# dw-probe-v1_0.net
KiCad netlist of a schematic drawn in EAGLE
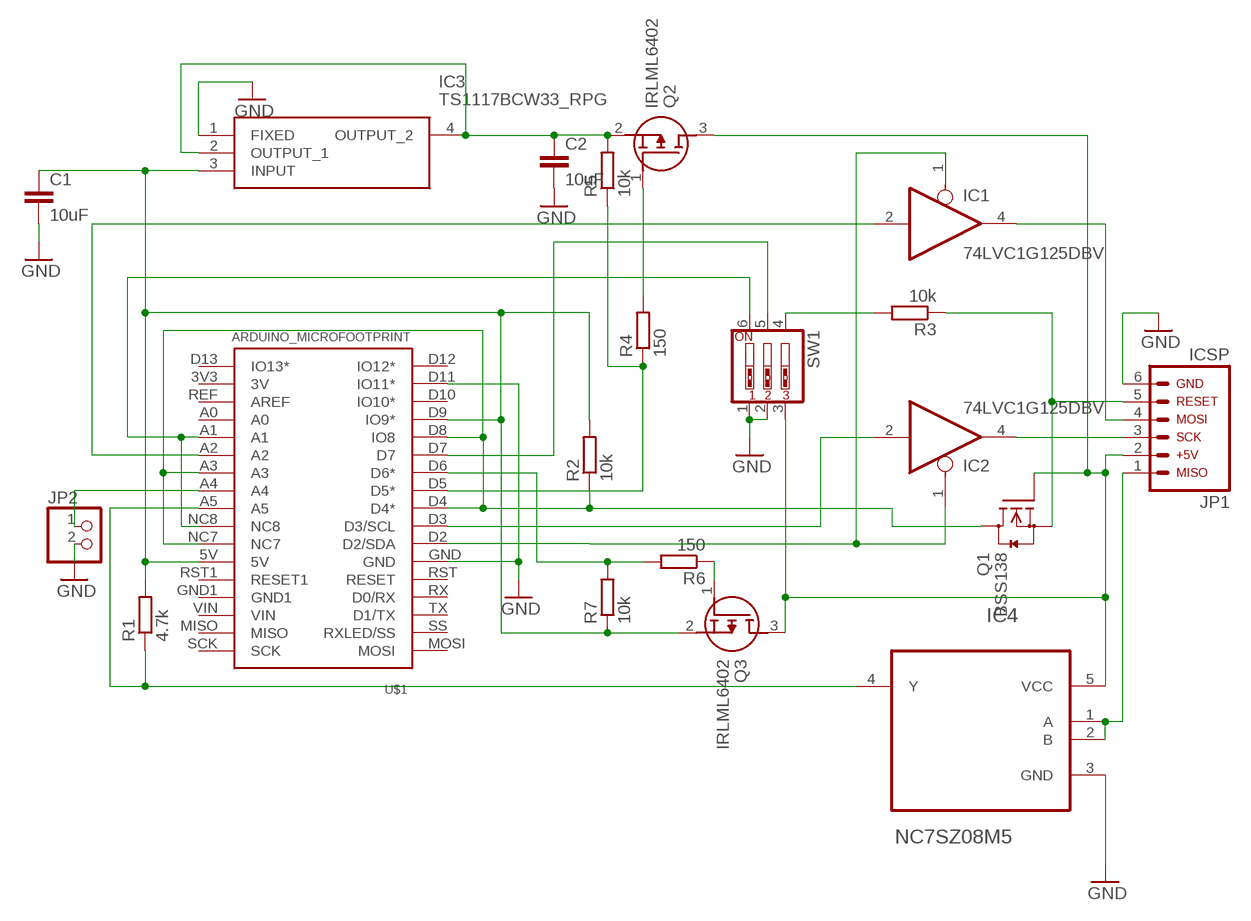
[diagram p0: schematic, sheet 1]

(export (version "E")
  (design (tool "Eeschema 10.0.6"))
  (components
    (comp (ref "C1")
      (value "10uF")
      (footprint "eagle-import:C0805")
      (libsource (lib "eagle-import") (part "C-EUC0805"))
    )
    (comp (ref "C2")
      (value "10uF")
      (footprint "eagle-import:C0805")
      (libsource (lib "eagle-import") (part "C-EUC0805"))
    )
    (comp (ref "IC1")
      (value "74LVC1G125DBV")
      (footprint "eagle-import:SOT23-5")
      (libsource (lib "eagle-import") (part "741G125DBVLVC"))
    )
    (comp (ref "IC2")
      (value "74LVC1G125DBV")
      (footprint "eagle-import:SOT23-5")
      (libsource (lib "eagle-import") (part "741G125DBVLVC"))
    )
    (comp (ref "IC3")
      (value "TS1117BCW33_RPG")
      (footprint "eagle-import:SOT230P700X190-4N")
      (fields
        (field (name "ARROW_PART_NUMBER") "TS1117BCW33 RPG")
        (field (name "MOUSER_PART_NUMBER") "821-TS1117BCW33RPG")
      )
      (libsource (lib "eagle-import") (part "TS1117BCW33_RPG"))
    )
    (comp (ref "IC4")
      (value "NC7SZ08M5")
      (footprint "eagle-import:SOT95P280X145-5N")
      (fields (field (name "MF") "ON Semiconductor"))
      (libsource (lib "eagle-import") (part "NC7SZ08M5"))
    )
    (comp (ref "JP1")
      (value "ARDUINO_CONN-ICSP")
      (footprint "eagle-import:CONN-2X03")
      (libsource (lib "eagle-import") (part "ARDUINO_CONN-ICSP"))
    )
    (comp (ref "JP2")
      (value "PINHD-1X2")
      (footprint "eagle-import:1X02")
      (libsource (lib "eagle-import") (part "PINHD-1X2"))
    )
    (comp (ref "Q1")
      (value "BSS138")
      (footprint "eagle-import:SOT23")
      (libsource (lib "eagle-import") (part "BSS138"))
    )
    (comp (ref "Q2")
      (value "IRLML6402")
      (footprint "eagle-import:SOT95P237X112-3N")
      (libsource (lib "eagle-import") (part "IRLML6402"))
    )
    (comp (ref "Q3")
      (value "IRLML6402")
      (footprint "eagle-import:SOT95P237X112-3N")
      (libsource (lib "eagle-import") (part "IRLML6402"))
    )
    (comp (ref "R1")
      (value "4.7k")
      (footprint "eagle-import:R0805")
      (libsource (lib "eagle-import") (part "R-EU_R0805"))
    )
    (comp (ref "R2")
      (value "10k")
      (footprint "eagle-import:R0805")
      (libsource (lib "eagle-import") (part "R-EU_R0805"))
    )
    (comp (ref "R3")
      (value "10k")
      (footprint "eagle-import:R0805")
      (libsource (lib "eagle-import") (part "R-EU_R0805"))
    )
    (comp (ref "R4")
      (value "150")
      (footprint "eagle-import:R0805")
      (libsource (lib "eagle-import") (part "R-EU_R0805"))
    )
    (comp (ref "R5")
      (value "10k")
      (footprint "eagle-import:R0805")
      (libsource (lib "eagle-import") (part "R-EU_R0805"))
    )
    (comp (ref "R6")
      (value "150")
      (footprint "eagle-import:R0805")
      (libsource (lib "eagle-import") (part "R-EU_R0805"))
    )
    (comp (ref "R7")
      (value "10k")
      (footprint "eagle-import:R0805")
      (libsource (lib "eagle-import") (part "R-EU_R0805"))
    )
    (comp (ref "SW1")
      (value "SW_DIP-3")
      (footprint "eagle-import:EDG-03")
      (libsource (lib "eagle-import") (part "SW_DIP-3"))
    )
    (comp (ref "U$1")
      (value "ARDUINO_MICROFOOTPRINT")
      (footprint "eagle-import:ARDUINO-MICRO")
      (libsource (lib "eagle-import") (part "ARDUINO_MICROFOOTPRINT"))
    )
  )
  (nets
    (net (code "1") (name "GND") (class "Default")
      (node (ref "C1") (pin "2") (pinfunction "2_2") (pintype "passive"))
      (node (ref "C2") (pin "2") (pinfunction "2_2") (pintype "passive"))
      (node (ref "IC3") (pin "1") (pinfunction "FIXED_1") (pintype "bidirectional"))
      (node (ref "IC4") (pin "3") (pinfunction "GND_3") (pintype "passive"))
      (node (ref "JP1") (pin "6") (pinfunction "6_6") (pintype "passive"))
      (node (ref "JP2") (pin "2") (pinfunction "2_2") (pintype "passive"))
      (node (ref "SW1") (pin "1") (pinfunction "1_1") (pintype "passive"))
      (node (ref "SW1") (pin "2") (pinfunction "2_2") (pintype "passive"))
      (node (ref "U$1") (pin "D11") (pinfunction "IO11*_D11") (pintype "bidirectional"))
      (node (ref "U$1") (pin "GND") (pinfunction "GND_GND") (pintype "bidirectional"))
    )
    (net (code "2") (name "Net-(IC1A-I)") (class "Default")
      (node (ref "IC1") (pin "2") (pinfunction "I_2") (pintype "input"))
      (node (ref "U$1") (pin "A2") (pinfunction "A2_A2") (pintype "bidirectional"))
    )
    (net (code "3") (name "Net-(IC1A-O)") (class "Default")
      (node (ref "IC1") (pin "4") (pinfunction "O_4") (pintype "tri_state"))
      (node (ref "JP1") (pin "4") (pinfunction "4_4") (pintype "passive"))
    )
    (net (code "4") (name "Net-(IC1A-OE)") (class "Default")
      (node (ref "IC1") (pin "1") (pinfunction "OE_1") (pintype "input"))
      (node (ref "IC2") (pin "1") (pinfunction "OE_1") (pintype "input"))
      (node (ref "U$1") (pin "D2") (pinfunction "D2/SDA_D2") (pintype "bidirectional"))
    )
    (net (code "5") (name "Net-(IC2A-I)") (class "Default")
      (node (ref "IC2") (pin "2") (pinfunction "I_2") (pintype "input"))
      (node (ref "U$1") (pin "D3") (pinfunction "D3/SCL_D3") (pintype "bidirectional"))
    )
    (net (code "6") (name "Net-(IC2A-O)") (class "Default")
      (node (ref "IC2") (pin "4") (pinfunction "O_4") (pintype "tri_state"))
      (node (ref "JP1") (pin "3") (pinfunction "3_3") (pintype "passive"))
    )
    (net (code "7") (name "Net-(IC3-INPUT)") (class "Default")
      (node (ref "C1") (pin "1") (pinfunction "1_1") (pintype "passive"))
      (node (ref "IC3") (pin "3") (pinfunction "INPUT_3") (pintype "bidirectional"))
      (node (ref "Q3") (pin "2") (pinfunction "S_2") (pintype "bidirectional"))
      (node (ref "R1") (pin "2") (pinfunction "2_2") (pintype "passive"))
      (node (ref "R2") (pin "2") (pinfunction "2_2") (pintype "passive"))
      (node (ref "R7") (pin "1") (pinfunction "1_1") (pintype "passive"))
      (node (ref "U$1") (pin "5V") (pinfunction "5V_5V") (pintype "bidirectional"))
      (node (ref "U$1") (pin "D9") (pinfunction "IO9*_D9") (pintype "bidirectional"))
    )
    (net (code "8") (name "Net-(IC3-OUTPUT_1)") (class "Default")
      (node (ref "C2") (pin "1") (pinfunction "1_1") (pintype "passive"))
      (node (ref "IC3") (pin "2") (pinfunction "OUTPUT_1_2") (pintype "bidirectional"))
      (node (ref "IC3") (pin "4") (pinfunction "OUTPUT_2_4") (pintype "bidirectional"))
      (node (ref "Q2") (pin "2") (pinfunction "S_2") (pintype "bidirectional"))
      (node (ref "R5") (pin "2") (pinfunction "2_2") (pintype "passive"))
    )
    (net (code "9") (name "Net-(IC4-A)") (class "Default")
      (node (ref "IC4") (pin "1") (pinfunction "A_1") (pintype "input"))
      (node (ref "IC4") (pin "2") (pinfunction "B_2") (pintype "input"))
      (node (ref "JP1") (pin "1") (pinfunction "1_1") (pintype "passive"))
    )
    (net (code "10") (name "Net-(IC4-VCC)") (class "Default")
      (node (ref "IC4") (pin "5") (pinfunction "VCC_5") (pintype "power_in"))
      (node (ref "JP1") (pin "2") (pinfunction "2_2") (pintype "passive"))
      (node (ref "Q1") (pin "1") (pinfunction "G_1") (pintype "passive"))
      (node (ref "Q2") (pin "3") (pinfunction "D_3") (pintype "bidirectional"))
      (node (ref "Q3") (pin "3") (pinfunction "D_3") (pintype "bidirectional"))
      (node (ref "SW1") (pin "3") (pinfunction "3_3") (pintype "passive"))
    )
    (net (code "11") (name "Net-(IC4-Y)") (class "Default")
      (node (ref "IC4") (pin "4") (pinfunction "Y_4") (pintype "output"))
      (node (ref "R1") (pin "1") (pinfunction "1_1") (pintype "passive"))
      (node (ref "U$1") (pin "A5") (pinfunction "A5_A5") (pintype "bidirectional"))
    )
    (net (code "12") (name "Net-(JP2-Pad1)") (class "Default")
      (node (ref "JP2") (pin "1") (pinfunction "1_1") (pintype "passive"))
      (node (ref "U$1") (pin "A4") (pinfunction "A4_A4") (pintype "bidirectional"))
    )
    (net (code "13") (name "Net-(Q1-D)") (class "Default")
      (node (ref "Q1") (pin "3") (pinfunction "D_3") (pintype "passive"))
      (node (ref "R2") (pin "1") (pinfunction "1_1") (pintype "passive"))
      (node (ref "U$1") (pin "A3") (pinfunction "A3_A3") (pintype "bidirectional"))
      (node (ref "U$1") (pin "D4") (pinfunction "D4*_D4") (pintype "bidirectional"))
      (node (ref "U$1") (pin "D8") (pinfunction "IO8_D8") (pintype "bidirectional"))
      (node (ref "U$1") (pin "NC7") (pinfunction "NC7_NC7") (pintype "bidirectional"))
    )
    (net (code "14") (name "Net-(Q1-S)") (class "Default")
      (node (ref "JP1") (pin "5") (pinfunction "5_5") (pintype "passive"))
      (node (ref "Q1") (pin "2") (pinfunction "S_2") (pintype "passive"))
      (node (ref "R3") (pin "1") (pinfunction "1_1") (pintype "passive"))
    )
    (net (code "15") (name "Net-(Q2-G)") (class "Default")
      (node (ref "Q2") (pin "1") (pinfunction "G_1") (pintype "bidirectional"))
      (node (ref "R4") (pin "2") (pinfunction "2_2") (pintype "passive"))
    )
    (net (code "16") (name "Net-(Q3-G)") (class "Default")
      (node (ref "Q3") (pin "1") (pinfunction "G_1") (pintype "bidirectional"))
      (node (ref "R6") (pin "1") (pinfunction "1_1") (pintype "passive"))
    )
    (net (code "17") (name "Net-(R3-Pad2)") (class "Default")
      (node (ref "R3") (pin "2") (pinfunction "2_2") (pintype "passive"))
      (node (ref "SW1") (pin "4") (pinfunction "4_4") (pintype "passive"))
    )
    (net (code "18") (name "Net-(SW1-Pad5)") (class "Default")
      (node (ref "SW1") (pin "5") (pinfunction "5_5") (pintype "passive"))
      (node (ref "U$1") (pin "D7") (pinfunction "D7_D7") (pintype "bidirectional"))
    )
    (net (code "19") (name "Net-(SW1-Pad6)") (class "Default")
      (node (ref "SW1") (pin "6") (pinfunction "6_6") (pintype "passive"))
      (node (ref "U$1") (pin "A1") (pinfunction "A1_A1") (pintype "bidirectional"))
      (node (ref "U$1") (pin "NC8") (pinfunction "NC8_NC8") (pintype "bidirectional"))
    )
    (net (code "20") (name "Net-(U$1-D5*)") (class "Default")
      (node (ref "R4") (pin "1") (pinfunction "1_1") (pintype "passive"))
      (node (ref "R5") (pin "1") (pinfunction "1_1") (pintype "passive"))
      (node (ref "U$1") (pin "D5") (pinfunction "D5*_D5") (pintype "bidirectional"))
    )
    (net (code "21") (name "Net-(U$1-D6*)") (class "Default")
      (node (ref "R6") (pin "2") (pinfunction "2_2") (pintype "passive"))
      (node (ref "R7") (pin "2") (pinfunction "2_2") (pintype "passive"))
      (node (ref "U$1") (pin "D6") (pinfunction "D6*_D6") (pintype "bidirectional"))
    )
    (net (code "22") (name "unconnected-(U$1-3V-Pad3V3)") (class "Default")
      (node (ref "U$1") (pin "3V3") (pinfunction "3V_3V3") (pintype "bidirectional"))
    )
    (net (code "23") (name "unconnected-(U$1-AREF-PadREF)") (class "Default")
      (node (ref "U$1") (pin "REF") (pinfunction "AREF_REF") (pintype "bidirectional"))
    )
    (net (code "24") (name "unconnected-(U$1-D0{slash}RX-PadRX)") (class "Default")
      (node (ref "U$1") (pin "RX") (pinfunction "D0/RX_RX") (pintype "bidirectional"))
    )
    (net (code "25") (name "unconnected-(U$1-D1{slash}TX-PadTX)") (class "Default")
      (node (ref "U$1") (pin "TX") (pinfunction "D1/TX_TX") (pintype "bidirectional"))
    )
    (net (code "26") (name "unconnected-(U$1-IO10*-PadD10)") (class "Default")
      (node (ref "U$1") (pin "D10") (pinfunction "IO10*_D10") (pintype "bidirectional"))
    )
    (net (code "27") (name "unconnected-(U$1-IO12*-PadD12)") (class "Default")
      (node (ref "U$1") (pin "D12") (pinfunction "IO12*_D12") (pintype "bidirectional"))
    )
    (net (code "28") (name "unconnected-(U$1-IO13*-PadD13)") (class "Default")
      (node (ref "U$1") (pin "D13") (pinfunction "IO13*_D13") (pintype "bidirectional"))
    )
    (net (code "29") (name "unconnected-(U$1-PadA0)") (class "Default")
      (node (ref "U$1") (pin "A0") (pinfunction "A0_A0") (pintype "bidirectional"))
    )
    (net (code "30") (name "unconnected-(U$1-PadGND1)") (class "Default")
      (node (ref "U$1") (pin "GND1") (pinfunction "GND1_GND1") (pintype "bidirectional"))
    )
    (net (code "31") (name "unconnected-(U$1-PadMISO)") (class "Default")
      (node (ref "U$1") (pin "MISO") (pinfunction "MISO_MISO") (pintype "bidirectional"))
    )
    (net (code "32") (name "unconnected-(U$1-PadMOSI)") (class "Default")
      (node (ref "U$1") (pin "MOSI") (pinfunction "MOSI_MOSI") (pintype "bidirectional"))
    )
    (net (code "33") (name "unconnected-(U$1-PadSCK)") (class "Default")
      (node (ref "U$1") (pin "SCK") (pinfunction "SCK_SCK") (pintype "bidirectional"))
    )
    (net (code "34") (name "unconnected-(U$1-PadVIN)") (class "Default")
      (node (ref "U$1") (pin "VIN") (pinfunction "VIN_VIN") (pintype "bidirectional"))
    )
    (net (code "35") (name "unconnected-(U$1-RESET-PadRST)") (class "Default")
      (node (ref "U$1") (pin "RST") (pinfunction "RESET_RST") (pintype "bidirectional"))
    )
    (net (code "36") (name "unconnected-(U$1-RESET1-PadRST1)") (class "Default")
      (node (ref "U$1") (pin "RST1") (pinfunction "RESET1_RST1") (pintype "bidirectional"))
    )
    (net (code "37") (name "unconnected-(U$1-RXLED{slash}SS-PadSS)") (class "Default")
      (node (ref "U$1") (pin "SS") (pinfunction "RXLED/SS_SS") (pintype "bidirectional"))
    )
  )
)
